# altimeter.net
KiCad netlist of a schematic drawn in EAGLE
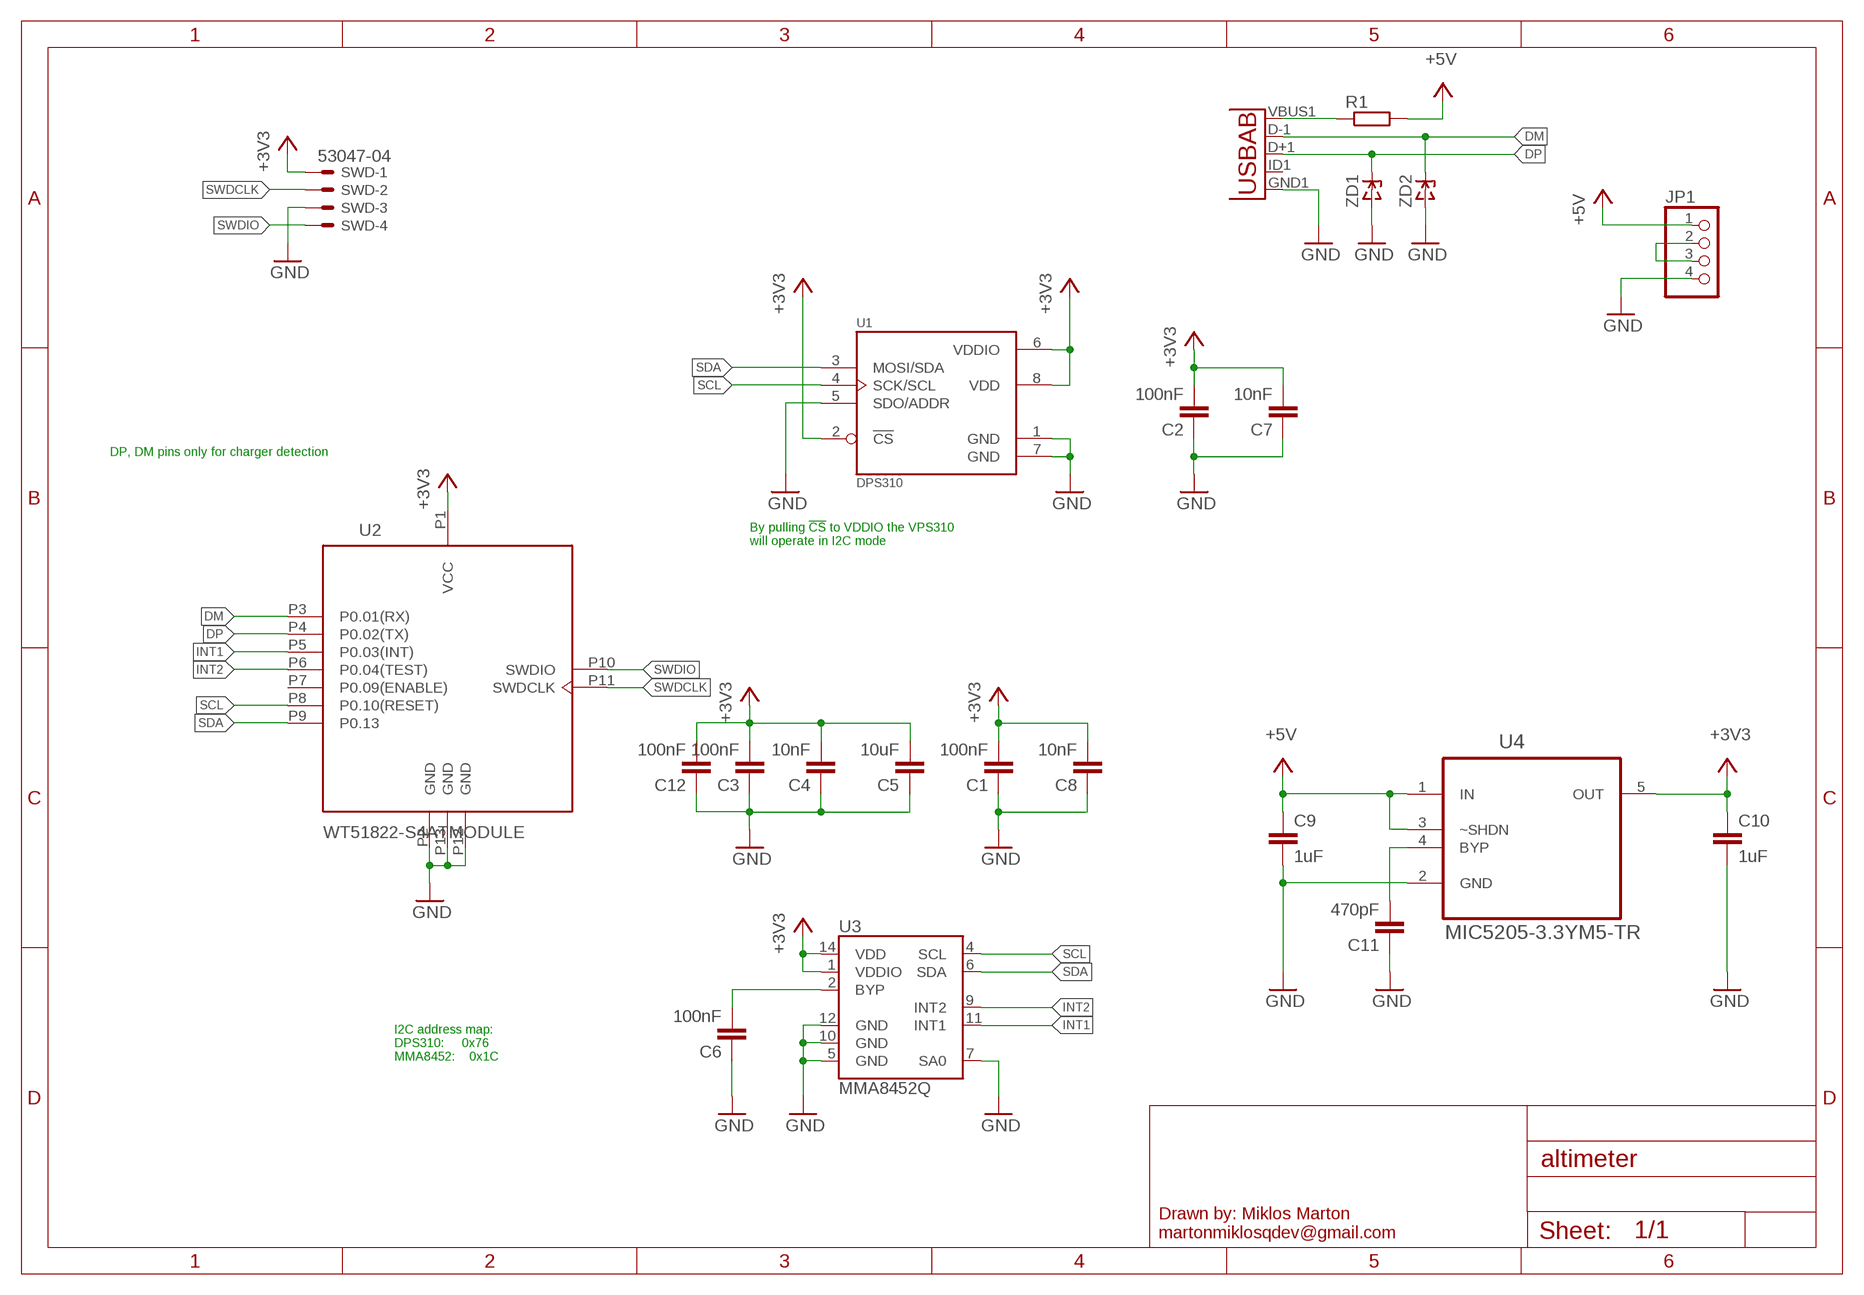
[diagram p0: schematic, sheet 1]

(export (version "E")
  (design (tool "Eeschema 10.0.6"))
  (components
    (comp (ref "C1")
      (value "100nF")
      (footprint "eagle-import:C0603")
      (libsource (lib "eagle-import") (part "rcl_334_C-EUC0603"))
    )
    (comp (ref "C2")
      (value "100nF")
      (footprint "eagle-import:C0603")
      (libsource (lib "eagle-import") (part "rcl_334_C-EUC0603"))
    )
    (comp (ref "C3")
      (value "100nF")
      (footprint "eagle-import:C0603")
      (libsource (lib "eagle-import") (part "rcl_334_C-EUC0603"))
    )
    (comp (ref "C4")
      (value "10nF")
      (footprint "eagle-import:C0603")
      (libsource (lib "eagle-import") (part "rcl_334_C-EUC0603"))
    )
    (comp (ref "C5")
      (value "10uF")
      (footprint "eagle-import:C0805")
      (libsource (lib "eagle-import") (part "rcl_334_C-EUC0805"))
    )
    (comp (ref "C6")
      (value "100nF")
      (footprint "eagle-import:C0603")
      (libsource (lib "eagle-import") (part "rcl_334_C-EUC0603"))
    )
    (comp (ref "C7")
      (value "10nF")
      (footprint "eagle-import:C0603")
      (libsource (lib "eagle-import") (part "rcl_334_C-EUC0603"))
    )
    (comp (ref "C8")
      (value "10nF")
      (footprint "eagle-import:C0603")
      (libsource (lib "eagle-import") (part "rcl_334_C-EUC0603"))
    )
    (comp (ref "C9")
      (value "1uF")
      (footprint "eagle-import:C0603")
      (libsource (lib "eagle-import") (part "C-EUC0603"))
    )
    (comp (ref "C10")
      (value "1uF")
      (footprint "eagle-import:C0603")
      (libsource (lib "eagle-import") (part "C-EUC0603"))
    )
    (comp (ref "C11")
      (value "470pF")
      (footprint "eagle-import:C0603")
      (libsource (lib "eagle-import") (part "rcl_334_C-EUC0603"))
    )
    (comp (ref "C12")
      (value "100nF")
      (footprint "eagle-import:C0603")
      (libsource (lib "eagle-import") (part "rcl_334_C-EUC0603"))
    )
    (comp (ref "JP1")
      (value "PINHD-1X4")
      (footprint "eagle-import:1X04")
      (libsource (lib "eagle-import") (part "PINHD-1X4"))
    )
    (comp (ref "R1")
      (value "R-EU_R0805")
      (footprint "eagle-import:R0805")
      (libsource (lib "eagle-import") (part "R-EU_R0805"))
    )
    (comp (ref "SWD")
      (value "53047-04")
      (footprint "eagle-import:53047-04")
      (fields (field (name "MF") "WALDOM/MOLEX") (field (name "MPN") "53047-0410"))
      (libsource (lib "eagle-import") (part "53?-04047"))
    )
    (comp (ref "U1")
      (value "DPS310")
      (footprint "eagle-import:LGA8S145X65P2X4_200X250X100")
      (libsource (lib "eagle-import") (part "DPS310"))
    )
    (comp (ref "U2")
      (value "WT51822-S4ATMODULE")
      (footprint "eagle-import:WT51822-S4AT")
      (libsource (lib "eagle-import") (part "WT51822-S4ATMODULE"))
    )
    (comp (ref "U3")
      (value "MMA8452Q")
      (footprint "eagle-import:QFN-16_0.5MM")
      (libsource (lib "eagle-import") (part "MMA8452Q"))
    )
    (comp (ref "U4")
      (value "MIC5205-3.3YM5-TR")
      (footprint "eagle-import:SOT95P280X145-5N")
      (fields (field (name "MPN") "LT1761ES5-3.3#TRMPBF"))
      (libsource (lib "eagle-import") (part "LT1761ES5-3.3TRMPBF"))
    )
    (comp (ref "USB")
      (value "USB-ABIN&OUT")
      (footprint "eagle-import:USB-AB-MICRO-SMD-V03-IN&OUT")
      (libsource (lib "eagle-import") (part "USB-ABIN&OUT"))
    )
    (comp (ref "ZD1")
      (value "ZENERSOD-123")
      (footprint "eagle-import:SOD-123")
      (libsource (lib "eagle-import") (part "ZENERSOD-123"))
    )
    (comp (ref "ZD2")
      (value "ZENERSOD-123")
      (footprint "eagle-import:SOD-123")
      (libsource (lib "eagle-import") (part "ZENERSOD-123"))
    )
  )
  (nets
    (net (code "1") (name "+3V3") (class "Default")
      (node (ref "C1") (pin "2") (pinfunction "2_2") (pintype "passive"))
      (node (ref "C10") (pin "1") (pinfunction "1_1") (pintype "passive"))
      (node (ref "C12") (pin "2") (pinfunction "2_2") (pintype "passive"))
      (node (ref "C2") (pin "2") (pinfunction "2_2") (pintype "passive"))
      (node (ref "C3") (pin "2") (pinfunction "2_2") (pintype "passive"))
      (node (ref "C4") (pin "2") (pinfunction "2_2") (pintype "passive"))
      (node (ref "C5") (pin "2") (pinfunction "2_2") (pintype "passive"))
      (node (ref "C7") (pin "2") (pinfunction "2_2") (pintype "passive"))
      (node (ref "C8") (pin "2") (pinfunction "2_2") (pintype "passive"))
      (node (ref "SWD") (pin "1") (pinfunction "S_1") (pintype "passive"))
      (node (ref "U1") (pin "2") (pinfunction "~{CS}_2") (pintype "input"))
      (node (ref "U1") (pin "6") (pinfunction "VDDIO_6") (pintype "passive"))
      (node (ref "U1") (pin "8") (pinfunction "VDD_8") (pintype "passive"))
      (node (ref "U2") (pin "P1") (pinfunction "VCC_P1") (pintype "passive"))
      (node (ref "U3") (pin "1") (pinfunction "VDDIO_1") (pintype "passive"))
      (node (ref "U3") (pin "14") (pinfunction "VDD_14") (pintype "passive"))
      (node (ref "U4") (pin "5") (pinfunction "OUT_5") (pintype "passive"))
    )
    (net (code "2") (name "+5V") (class "Default")
      (node (ref "C9") (pin "1") (pinfunction "1_1") (pintype "passive"))
      (node (ref "JP1") (pin "1") (pinfunction "1_1") (pintype "passive"))
      (node (ref "R1") (pin "2") (pinfunction "2_2") (pintype "passive"))
      (node (ref "U4") (pin "1") (pinfunction "IN_1") (pintype "power_in"))
      (node (ref "U4") (pin "3") (pinfunction "~{SHDN}_3") (pintype "input"))
    )
    (net (code "3") (name "DM") (class "Default")
      (node (ref "U2") (pin "P3") (pinfunction "P0.01(RX)_P3") (pintype "bidirectional"))
      (node (ref "USB") (pin "D-1") (pinfunction "D-_D-1") (pintype "bidirectional"))
      (node (ref "ZD2") (pin "C") (pinfunction "C_C") (pintype "passive"))
    )
    (net (code "4") (name "DP") (class "Default")
      (node (ref "U2") (pin "P4") (pinfunction "P0.02(TX)_P4") (pintype "bidirectional"))
      (node (ref "USB") (pin "D+1") (pinfunction "D+_D+1") (pintype "bidirectional"))
      (node (ref "ZD1") (pin "C") (pinfunction "C_C") (pintype "passive"))
    )
    (net (code "5") (name "GND") (class "Default")
      (node (ref "C1") (pin "1") (pinfunction "1_1") (pintype "passive"))
      (node (ref "C10") (pin "2") (pinfunction "2_2") (pintype "passive"))
      (node (ref "C11") (pin "1") (pinfunction "1_1") (pintype "passive"))
      (node (ref "C12") (pin "1") (pinfunction "1_1") (pintype "passive"))
      (node (ref "C2") (pin "1") (pinfunction "1_1") (pintype "passive"))
      (node (ref "C3") (pin "1") (pinfunction "1_1") (pintype "passive"))
      (node (ref "C4") (pin "1") (pinfunction "1_1") (pintype "passive"))
      (node (ref "C5") (pin "1") (pinfunction "1_1") (pintype "passive"))
      (node (ref "C6") (pin "1") (pinfunction "1_1") (pintype "passive"))
      (node (ref "C7") (pin "1") (pinfunction "1_1") (pintype "passive"))
      (node (ref "C8") (pin "1") (pinfunction "1_1") (pintype "passive"))
      (node (ref "C9") (pin "2") (pinfunction "2_2") (pintype "passive"))
      (node (ref "JP1") (pin "4") (pinfunction "4_4") (pintype "passive"))
      (node (ref "SWD") (pin "3") (pinfunction "S_3") (pintype "passive"))
      (node (ref "U1") (pin "1") (pinfunction "GND_1") (pintype "passive"))
      (node (ref "U1") (pin "5") (pinfunction "SDO/ADDR_5") (pintype "output"))
      (node (ref "U1") (pin "7") (pinfunction "GND_7") (pintype "passive"))
      (node (ref "U2") (pin "P12") (pinfunction "GND_P12") (pintype "passive"))
      (node (ref "U2") (pin "P13") (pinfunction "GND_P13") (pintype "passive"))
      (node (ref "U2") (pin "P2") (pinfunction "GND_P2") (pintype "passive"))
      (node (ref "U3") (pin "10") (pinfunction "GND_10") (pintype "passive"))
      (node (ref "U3") (pin "12") (pinfunction "GND_12") (pintype "passive"))
      (node (ref "U3") (pin "5") (pinfunction "GND_5") (pintype "passive"))
      (node (ref "U3") (pin "7") (pinfunction "SA0_7") (pintype "input"))
      (node (ref "U4") (pin "2") (pinfunction "GND_2") (pintype "passive"))
      (node (ref "USB") (pin "GND1") (pinfunction "GND_GND1") (pintype "bidirectional"))
      (node (ref "ZD1") (pin "A") (pinfunction "A_A") (pintype "passive"))
      (node (ref "ZD2") (pin "A") (pinfunction "A_A") (pintype "passive"))
    )
    (net (code "6") (name "INT1") (class "Default")
      (node (ref "U2") (pin "P5") (pinfunction "P0.03(INT)_P5") (pintype "bidirectional"))
      (node (ref "U3") (pin "11") (pinfunction "INT1_11") (pintype "output"))
    )
    (net (code "7") (name "INT2") (class "Default")
      (node (ref "U2") (pin "P6") (pinfunction "P0.04(TEST)_P6") (pintype "bidirectional"))
      (node (ref "U3") (pin "9") (pinfunction "INT2_9") (pintype "output"))
    )
    (net (code "8") (name "Net-(JP1-Pad2)") (class "Default")
      (node (ref "JP1") (pin "2") (pinfunction "2_2") (pintype "passive"))
      (node (ref "JP1") (pin "3") (pinfunction "3_3") (pintype "passive"))
    )
    (net (code "9") (name "Net-(U3-BYP)") (class "Default")
      (node (ref "C6") (pin "2") (pinfunction "2_2") (pintype "passive"))
      (node (ref "U3") (pin "2") (pinfunction "BYP_2") (pintype "passive"))
    )
    (net (code "10") (name "Net-(U4-BYP)") (class "Default")
      (node (ref "C11") (pin "2") (pinfunction "2_2") (pintype "passive"))
      (node (ref "U4") (pin "4") (pinfunction "BYP_4") (pintype "passive"))
    )
    (net (code "11") (name "Net-(USB-VBUS)") (class "Default")
      (node (ref "R1") (pin "1") (pinfunction "1_1") (pintype "passive"))
      (node (ref "USB") (pin "VBUS1") (pinfunction "VBUS_VBUS1") (pintype "bidirectional"))
    )
    (net (code "12") (name "SCL") (class "Default")
      (node (ref "U1") (pin "4") (pinfunction "SCK/SCL_4") (pintype "input"))
      (node (ref "U2") (pin "P8") (pinfunction "P0.10(RESET)_P8") (pintype "bidirectional"))
      (node (ref "U3") (pin "4") (pinfunction "SCL_4") (pintype "input"))
    )
    (net (code "13") (name "SDA") (class "Default")
      (node (ref "U1") (pin "3") (pinfunction "MOSI/SDA_3") (pintype "bidirectional"))
      (node (ref "U2") (pin "P9") (pinfunction "P0.13_P9") (pintype "bidirectional"))
      (node (ref "U3") (pin "6") (pinfunction "SDA_6") (pintype "bidirectional"))
    )
    (net (code "14") (name "SWDCLK") (class "Default")
      (node (ref "SWD") (pin "2") (pinfunction "S_2") (pintype "passive"))
      (node (ref "U2") (pin "P11") (pinfunction "SWDCLK_P11") (pintype "input"))
    )
    (net (code "15") (name "SWDIO") (class "Default")
      (node (ref "SWD") (pin "4") (pinfunction "S_4") (pintype "passive"))
      (node (ref "U2") (pin "P10") (pinfunction "SWDIO_P10") (pintype "bidirectional"))
    )
    (net (code "16") (name "unconnected-(U2-P0.09(ENABLE)-PadP7)") (class "Default")
      (node (ref "U2") (pin "P7") (pinfunction "P0.09(ENABLE)_P7") (pintype "bidirectional"))
    )
    (net (code "17") (name "unconnected-(USB-USBID-PadID1)") (class "Default")
      (node (ref "USB") (pin "ID1") (pinfunction "USBID_ID1") (pintype "bidirectional"))
    )
  )
)
